# Buck.net
KiCad netlist of a schematic drawn in Altium Designer
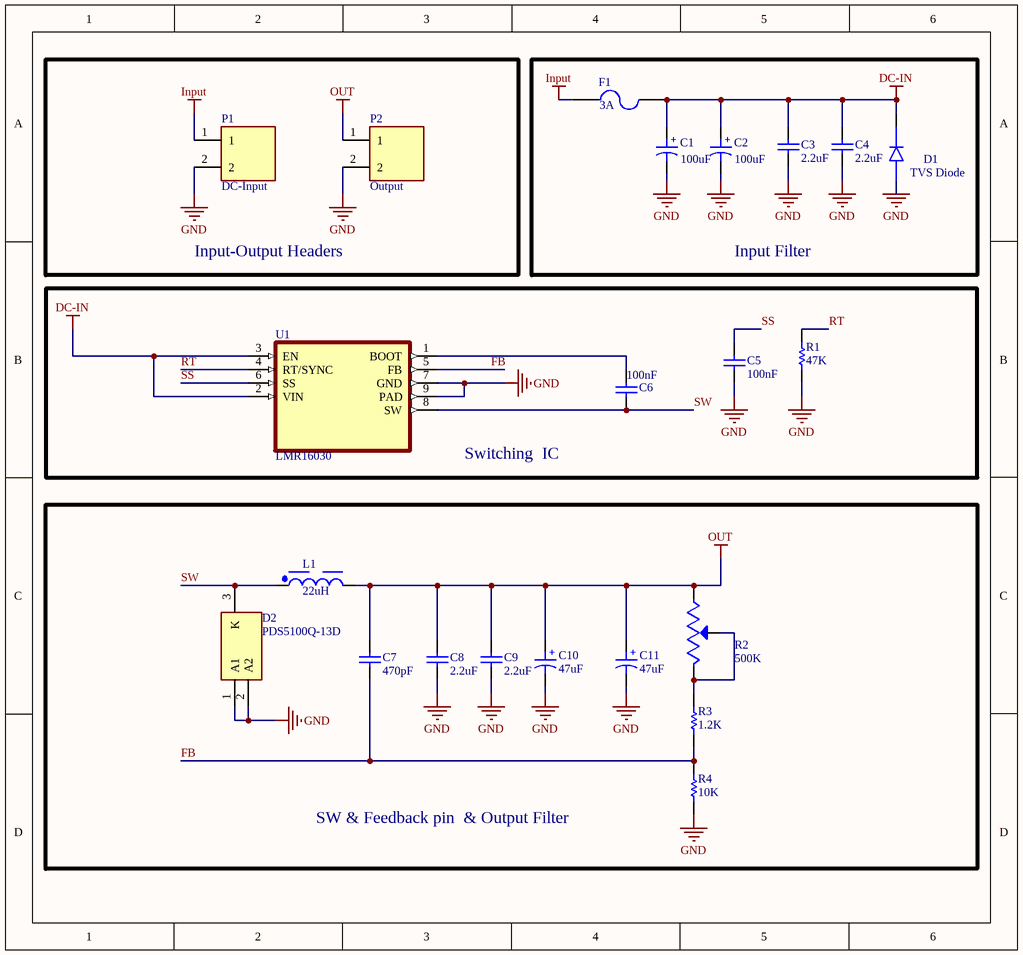
[diagram p0: Buck.SchDoc]

(export (version "E")
  (design (tool "Eeschema 10.0.6"))
  (components
    (comp (ref "C1")
      (value "100uF")
      (footprint "CAPACITOR-10mm")
      (description "100uF-63V")
      (libsource (lib "General") (part "Capacitor Electrolytic"))
    )
    (comp (ref "C2")
      (value "100uF")
      (footprint "CAPACITOR-10mm")
      (description "100uF-63V")
      (libsource (lib "General") (part "Capacitor Electrolytic"))
    )
    (comp (ref "C3")
      (value "2.2uF")
      (footprint "CAPACITOR-0805")
      (description "2.2uF-100V-0805-X7R")
      (libsource (lib "General") (part "Capacitor"))
    )
    (comp (ref "C4")
      (value "2.2uF")
      (footprint "CAPACITOR-0805")
      (description "2.2uF-100V-0805-X7R")
      (libsource (lib "General") (part "Capacitor"))
    )
    (comp (ref "C5")
      (value "100nF")
      (footprint "CAPACITOR-0805")
      (description "100nF-100V-0805-X7R")
      (libsource (lib "General") (part "Capacitor"))
    )
    (comp (ref "C6")
      (value "100nF")
      (footprint "CAPACITOR-0805")
      (description "100nF-100V-0805-X7R")
      (libsource (lib "General") (part "Capacitor"))
    )
    (comp (ref "C7")
      (value "470pF")
      (footprint "CAPACITOR-0603")
      (description "470pF-100V-0603-C0G")
      (libsource (lib "General") (part "Capacitor"))
    )
    (comp (ref "C8")
      (value "2.2uF")
      (footprint "CAPACITOR-0805")
      (description "2.2uF-100V-0805-X7R")
      (libsource (lib "General") (part "Capacitor"))
    )
    (comp (ref "C9")
      (value "2.2uF")
      (footprint "CAPACITOR-0805")
      (description "2.2uF-100V-0805-X7R")
      (libsource (lib "General") (part "Capacitor"))
    )
    (comp (ref "C10")
      (value "47uF")
      (footprint "CAPACITOR-10mm")
      (description "47uF-80V")
      (libsource (lib "General") (part "Capacitor Electrolytic"))
    )
    (comp (ref "C11")
      (value "47uF")
      (footprint "CAPACITOR-10mm")
      (description "47uF-80V")
      (libsource (lib "General") (part "Capacitor Electrolytic"))
    )
    (comp (ref "D1")
      (value "TVS Diode")
      (footprint "SMB DIODE")
      (description "SMB-J51A")
      (libsource (lib "General") (part "Diode"))
    )
    (comp (ref "D2")
      (value "PDS5100Q-13D")
      (footprint "PDS5100Q13D")
      (libsource (lib "General") (part "Schottky Diode"))
    )
    (comp (ref "F1")
      (value "3A")
      (footprint "FUSE-1206")
      (description "PTC Fuse- 3A- 1206")
      (libsource (lib "General") (part "Fuse"))
    )
    (comp (ref "L1")
      (value "22uH")
      (footprint "Power Inductor")
      (description "22uH-TMPC1265HP-220MG-D")
      (libsource (lib "General") (part "Power Inductor"))
    )
    (comp (ref "P1")
      (value "DC-Input")
      (footprint "2 Pin Terminal Block 5mm Pitch")
      (description "KF301-5.0-2pin")
      (libsource (lib "General") (part "Header 2 pin"))
    )
    (comp (ref "P2")
      (value "Output")
      (footprint "2 Pin Terminal Block 5mm Pitch")
      (description "KF301-5.0-2pin")
      (libsource (lib "General") (part "Header 2 pin"))
    )
    (comp (ref "R1")
      (value "47K")
      (footprint "Resistor-0805")
      (description "Resisto47K-0805")
      (libsource (lib "General") (part "Resistor"))
    )
    (comp (ref "R2")
      (value "500K")
      (footprint "Multi turn")
      (description "500K multi turn")
      (libsource (lib "General") (part "Multi Turn"))
    )
    (comp (ref "R3")
      (value "1.2K")
      (footprint "Resistor-0805")
      (description "Resistor 100K-0805")
      (libsource (lib "General") (part "Resistor"))
    )
    (comp (ref "R4")
      (value "10K")
      (footprint "Resistor-0805")
      (description "Resistor 10K-0805")
      (libsource (lib "General") (part "Resistor"))
    )
    (comp (ref "U1")
      (value "LMR16030")
      (footprint "LMR16030")
      (description "LMR16030-Switching Regulator")
      (libsource (lib "General") (part "LMR16030"))
    )
  )
  (nets
    (net (code "1") (name "/FB") (class "Default")
      (node (ref "C7") (pin "1") (pinfunction "1_1") (pintype "passive"))
      (node (ref "R3") (pin "1") (pinfunction "1_1") (pintype "passive"))
      (node (ref "R4") (pin "2") (pinfunction "2_2") (pintype "passive"))
      (node (ref "U1") (pin "5") (pinfunction "FB_5") (pintype "output"))
    )
    (net (code "2") (name "/RT") (class "Default")
      (node (ref "R1") (pin "2") (pinfunction "2_2") (pintype "passive"))
      (node (ref "U1") (pin "4") (pinfunction "RT/SYNC_4") (pintype "input"))
    )
    (net (code "3") (name "/SS") (class "Default")
      (node (ref "C5") (pin "1") (pinfunction "1_1") (pintype "passive"))
      (node (ref "U1") (pin "6") (pinfunction "SS_6") (pintype "input"))
    )
    (net (code "4") (name "/SW") (class "Default")
      (node (ref "C6") (pin "2") (pinfunction "2_2") (pintype "passive"))
      (node (ref "D2") (pin "3") (pinfunction "K_3") (pintype "passive"))
      (node (ref "L1") (pin "1") (pinfunction "1_1") (pintype "passive"))
      (node (ref "U1") (pin "8") (pinfunction "SW_8") (pintype "output"))
    )
    (net (code "5") (name "DC-IN") (class "Default")
      (node (ref "C1") (pin "1") (pinfunction "1_1") (pintype "passive"))
      (node (ref "C2") (pin "1") (pinfunction "1_1") (pintype "passive"))
      (node (ref "C3") (pin "2") (pinfunction "2_2") (pintype "passive"))
      (node (ref "C4") (pin "2") (pinfunction "2_2") (pintype "passive"))
      (node (ref "D1") (pin "C") (pinfunction "C_C") (pintype "passive"))
      (node (ref "F1") (pin "2") (pinfunction "2_2") (pintype "passive"))
      (node (ref "U1") (pin "2") (pinfunction "VIN_2") (pintype "input"))
      (node (ref "U1") (pin "3") (pinfunction "EN_3") (pintype "input"))
    )
    (net (code "6") (name "GND") (class "Default")
      (node (ref "C1") (pin "2") (pinfunction "2_2") (pintype "passive"))
      (node (ref "C10") (pin "2") (pinfunction "2_2") (pintype "passive"))
      (node (ref "C11") (pin "2") (pinfunction "2_2") (pintype "passive"))
      (node (ref "C2") (pin "2") (pinfunction "2_2") (pintype "passive"))
      (node (ref "C3") (pin "1") (pinfunction "1_1") (pintype "passive"))
      (node (ref "C4") (pin "1") (pinfunction "1_1") (pintype "passive"))
      (node (ref "C5") (pin "2") (pinfunction "2_2") (pintype "passive"))
      (node (ref "C8") (pin "1") (pinfunction "1_1") (pintype "passive"))
      (node (ref "C9") (pin "1") (pinfunction "1_1") (pintype "passive"))
      (node (ref "D1") (pin "A") (pinfunction "A_A") (pintype "passive"))
      (node (ref "D2") (pin "1") (pinfunction "A1_1") (pintype "passive"))
      (node (ref "D2") (pin "2") (pinfunction "A2_2") (pintype "passive"))
      (node (ref "P1") (pin "2") (pinfunction "2_2") (pintype "passive"))
      (node (ref "P2") (pin "2") (pinfunction "2_2") (pintype "passive"))
      (node (ref "R1") (pin "1") (pinfunction "1_1") (pintype "passive"))
      (node (ref "R4") (pin "1") (pinfunction "1_1") (pintype "passive"))
      (node (ref "U1") (pin "7") (pinfunction "GND_7") (pintype "output"))
      (node (ref "U1") (pin "9") (pinfunction "PAD_9") (pintype "output"))
    )
    (net (code "7") (name "Input") (class "Default")
      (node (ref "F1") (pin "1") (pinfunction "1_1") (pintype "passive"))
      (node (ref "P1") (pin "1") (pinfunction "1_1") (pintype "passive"))
    )
    (net (code "8") (name "Net-(R2-CW)") (class "Default")
      (node (ref "R2") (pin "2") (pinfunction "WIPER_2") (pintype "passive"))
      (node (ref "R2") (pin "3") (pinfunction "CW_3") (pintype "passive"))
      (node (ref "R3") (pin "2") (pinfunction "2_2") (pintype "passive"))
    )
    (net (code "9") (name "Net-(U1-BOOT)") (class "Default")
      (node (ref "C6") (pin "1") (pinfunction "1_1") (pintype "passive"))
      (node (ref "U1") (pin "1") (pinfunction "BOOT_1") (pintype "output"))
    )
    (net (code "10") (name "OUT") (class "Default")
      (node (ref "C10") (pin "1") (pinfunction "1_1") (pintype "passive"))
      (node (ref "C11") (pin "1") (pinfunction "1_1") (pintype "passive"))
      (node (ref "C7") (pin "2") (pinfunction "2_2") (pintype "passive"))
      (node (ref "C8") (pin "2") (pinfunction "2_2") (pintype "passive"))
      (node (ref "C9") (pin "2") (pinfunction "2_2") (pintype "passive"))
      (node (ref "L1") (pin "2") (pinfunction "2_2") (pintype "passive"))
      (node (ref "P2") (pin "1") (pinfunction "1_1") (pintype "passive"))
      (node (ref "R2") (pin "1") (pinfunction "CCW_1") (pintype "passive"))
    )
  )
)
